# 02_-_Power_Supplies_-_Copy.net
KiCad netlist of a schematic drawn in Altium Designer
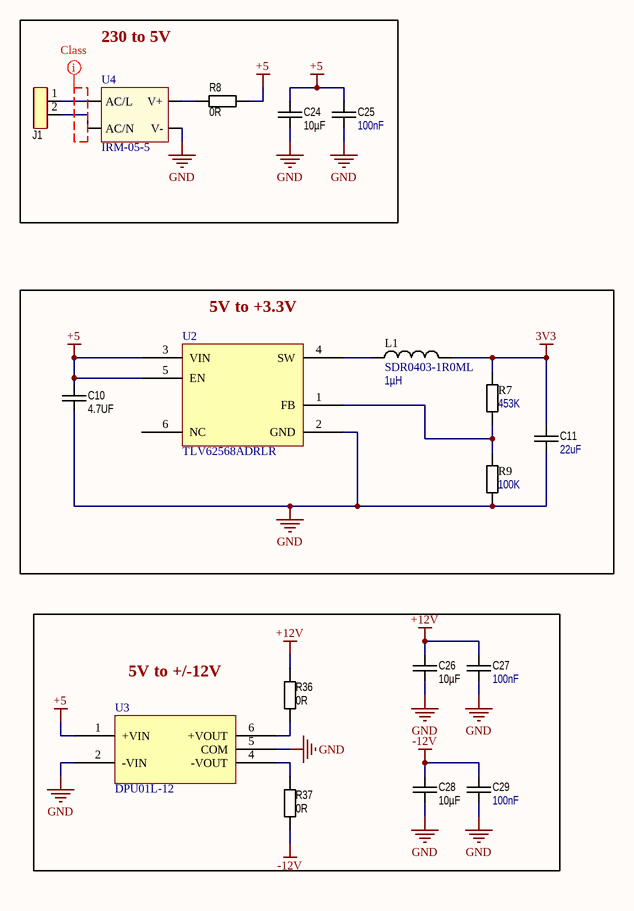
[diagram p0: [02] - Power_Supplies - Copy.SchDoc]

(export (version "E")
  (design (tool "Eeschema 10.0.6"))
  (components
    (comp (ref "C10")
      (value "4.7UF")
      (footprint "CAP 0603/1608")
      (description "4.7µF ±10% 6.3V Ceramic Capacitor X5R 0603 (1608 Metric)")
      (fields (field (name "PARTNUMBER") "C0603C475K9PACTU") (field (name "MANUFACTURER") "KEMET"))
      (libsource (lib "myLibrary") (part "CAPC_4.7UF_0603_6.3V"))
    )
    (comp (ref "C11")
      (value "22uF")
      (footprint "CAP 0603/1608")
      (description "22µF ±20% 6.3V Ceramic Capacitor X5R 0603 (1608 Metric)")
      (fields
        (field (name "PARTNUMBER") "GRM188R60J226MEA0D")
        (field (name "MANUFACTURER") "Murata Electronics")
      )
      (libsource (lib "myLibrary") (part "CAPC_22uF_0603_6.3V"))
    )
    (comp (ref "C24")
      (value "10µF")
      (footprint "CAP 0603/1608")
      (description "10µF ±20% 25V Ceramic Capacitor X5R 0603 (1608 Metric)")
      (fields
        (field (name "PARTNUMBER") "GRM188R61E106MA73D")
        (field (name "MANUFACTURER") "Murata Electronics")
      )
      (libsource (lib "myLibrary") (part "CAPC_10uF_0603_25V"))
    )
    (comp (ref "C25")
      (value "100nF")
      (footprint "CAP 0603/1608")
      (description "0.1µF ±20% 50V Ceramic Capacitor X7R 0603 (1608 Metric)")
      (fields (field (name "PARTNUMBER") "C0603C104M5RACTU") (field (name "MANUFACTURER") "KEMET"))
      (libsource (lib "myLibrary") (part "CAPC_100NF_0603_50V"))
    )
    (comp (ref "C26")
      (value "10µF")
      (footprint "CAP 0603/1608")
      (description "10µF ±20% 25V Ceramic Capacitor X5R 0603 (1608 Metric)")
      (fields
        (field (name "PARTNUMBER") "GRM188R61E106MA73D")
        (field (name "MANUFACTURER") "Murata Electronics")
      )
      (libsource (lib "myLibrary") (part "CAPC_10uF_0603_25V"))
    )
    (comp (ref "C27")
      (value "100nF")
      (footprint "CAP 0603/1608")
      (description "0.1µF ±20% 50V Ceramic Capacitor X7R 0603 (1608 Metric)")
      (fields (field (name "PARTNUMBER") "C0603C104M5RACTU") (field (name "MANUFACTURER") "KEMET"))
      (libsource (lib "myLibrary") (part "CAPC_100NF_0603_50V"))
    )
    (comp (ref "C28")
      (value "10µF")
      (footprint "CAP 0603/1608")
      (description "10µF ±20% 25V Ceramic Capacitor X5R 0603 (1608 Metric)")
      (fields
        (field (name "PARTNUMBER") "GRM188R61E106MA73D")
        (field (name "MANUFACTURER") "Murata Electronics")
      )
      (libsource (lib "myLibrary") (part "CAPC_10uF_0603_25V"))
    )
    (comp (ref "C29")
      (value "100nF")
      (footprint "CAP 0603/1608")
      (description "0.1µF ±20% 50V Ceramic Capacitor X7R 0603 (1608 Metric)")
      (fields (field (name "PARTNUMBER") "C0603C104M5RACTU") (field (name "MANUFACTURER") "KEMET"))
      (libsource (lib "myLibrary") (part "CAPC_100NF_0603_50V"))
    )
    (comp (ref "J1")
      (value "1985195")
      (footprint "BLK_02P_3.5MM")
      (description "2 Position Wire to Board Terminal Block 45° (135°) Angle with Board 0.138\" (3.50mm) Through Hole")
      (fields (field (name "MANUFACTURER") "Phoenix Contact"))
      (libsource (lib "myLibrary") (part "BLK_02_3.5"))
    )
    (comp (ref "L1")
      (value "SDR0403-1R0ML")
      (footprint "IND_NonStandard")
      (description "1µH Unshielded Wirewound Inductor 3.8A 33mOhm Max Nonstandard")
      (fields (field (name "MANUFACTURER") "Bourns Inc.") (field (name "ALTIUM_VALUE") "1µH"))
      (libsource (lib "myLibrary") (part "IND_1uH"))
    )
    (comp (ref "R7")
      (value "453K")
      (footprint "R0603")
      (description "453 kOhms ±0.1% 0.063W, 1/16W Chip Resistor 0603 (1608 Metric) Thin Film")
      (fields
        (field (name "PARTNUMBER") "RN73C1J453KBTD")
        (field (name "MANUFACTURER") "TE Connectivity Passive Product")
      )
      (libsource (lib "myLibrary") (part "RES_453k_0603_0.1%"))
    )
    (comp (ref "R8")
      (value "0R")
      (footprint "R0603")
      (description "RES 0R 0603 JUMPER")
      (fields (field (name "PARTNUMBER") "RC0603JR-070RL") (field (name "MANUFACTURER") "Yageo"))
      (libsource (lib "") (part "RES_0R_0603_JUMPER_1"))
    )
    (comp (ref "R9")
      (value "100K")
      (footprint "R0603")
      (description "100 kOhms ±0.1% 0.1W, 1/10W Chip Resistor 0603 (1608 Metric) Thin Film")
      (fields (field (name "PARTNUMBER") "RT0603BRD07100KL") (field (name "MANUFACTURER") "Yageo"))
      (libsource (lib "myLibrary") (part "RES_100k_0603_0.1%"))
    )
    (comp (ref "R36")
      (value "0R")
      (footprint "R0603")
      (description "RES 0R 0603 JUMPER")
      (fields (field (name "PARTNUMBER") "RC0603JR-070RL") (field (name "MANUFACTURER") "Yageo"))
      (libsource (lib "myLibrary") (part "RES_0R_0603_JUMPER"))
    )
    (comp (ref "R37")
      (value "0R")
      (footprint "R0603")
      (description "RES 0R 0603 JUMPER")
      (fields (field (name "PARTNUMBER") "RC0603JR-070RL") (field (name "MANUFACTURER") "Yageo"))
      (libsource (lib "myLibrary") (part "RES_0R_0603_JUMPER"))
    )
    (comp (ref "U2")
      (value "TLV62568ADRLR")
      (footprint "SOT-563")
      (description "Buck Switching Regulator IC Positive Adjustable 0.6V 1 Output 1A SOT-563, SOT-666")
      (fields (field (name "MANUFACTURER") "Texas Instruments"))
      (libsource (lib "myLibrary") (part "TLV62568ADRLR"))
    )
    (comp (ref "U3")
      (value "DPU01L-12")
      (footprint "SIP7")
      (description "Isolated Module DC DC Converter 2 Output 12V -12V 42mA, 42mA 4.5V - 5.5V Input")
      (fields (field (name "MANUFACTURER") "MEAN WELL USA Inc."))
      (libsource (lib "myLibrary") (part "DC/DC-DPU01L-12"))
    )
    (comp (ref "U4")
      (value "IRM-05-5")
      (footprint "IRM-05-5_DIP-4")
      (description "Enclosed AC DC Converter 1 Output 5V    1A 85 ~ 305 VAC, 120 ~ 430 VDC Input")
      (fields (field (name "MANUFACTURER") "MEAN WELL USA Inc."))
      (libsource (lib "myLibrary") (part "AC/DC-IRM-05-5"))
    )
  )
  (nets
    (net (code "1") (name "+5") (class "Default")
      (node (ref "C10") (pin "1") (pintype "passive"))
      (node (ref "C24") (pin "1") (pintype "passive"))
      (node (ref "C25") (pin "1") (pintype "passive"))
      (node (ref "R8") (pin "2") (pinfunction "2_2") (pintype "passive"))
      (node (ref "U2") (pin "3") (pinfunction "VIN_3") (pintype "passive"))
      (node (ref "U2") (pin "5") (pinfunction "EN_5") (pintype "passive"))
      (node (ref "U3") (pin "1") (pinfunction "+VIN_1") (pintype "passive"))
    )
    (net (code "2") (name "+12V") (class "Default")
      (node (ref "C26") (pin "1") (pintype "passive"))
      (node (ref "C27") (pin "1") (pintype "passive"))
      (node (ref "R36") (pin "2") (pinfunction "2_2") (pintype "passive"))
    )
    (net (code "3") (name "-12V") (class "Default")
      (node (ref "C28") (pin "1") (pintype "passive"))
      (node (ref "C29") (pin "1") (pintype "passive"))
      (node (ref "R37") (pin "1") (pinfunction "1_1") (pintype "passive"))
    )
    (net (code "4") (name "3V3") (class "Default")
      (node (ref "C11") (pin "1") (pintype "passive"))
      (node (ref "L1") (pin "2") (pinfunction "2_2") (pintype "passive"))
      (node (ref "R7") (pin "1") (pinfunction "1_1") (pintype "passive"))
    )
    (net (code "5") (name "GND") (class "Default")
      (node (ref "C10") (pin "2") (pintype "passive"))
      (node (ref "C11") (pin "2") (pintype "passive"))
      (node (ref "C24") (pin "2") (pintype "passive"))
      (node (ref "C25") (pin "2") (pintype "passive"))
      (node (ref "C26") (pin "2") (pintype "passive"))
      (node (ref "C27") (pin "2") (pintype "passive"))
      (node (ref "C28") (pin "2") (pintype "passive"))
      (node (ref "C29") (pin "2") (pintype "passive"))
      (node (ref "R9") (pin "2") (pinfunction "2_2") (pintype "passive"))
      (node (ref "U2") (pin "2") (pinfunction "GND_2") (pintype "passive"))
      (node (ref "U3") (pin "2") (pinfunction "-VIN_2") (pintype "passive"))
      (node (ref "U3") (pin "5") (pinfunction "COM_5") (pintype "passive"))
      (node (ref "U4") (pin "V-") (pinfunction "V-_V-") (pintype "passive"))
    )
    (net (code "6") (name "Net-(J1-Pad1)") (class "Default")
      (node (ref "J1") (pin "1") (pintype "passive"))
      (node (ref "U4") (pin "AC/L") (pinfunction "AC/L_AC/L") (pintype "passive"))
    )
    (net (code "7") (name "Net-(J1-Pad2)") (class "Default")
      (node (ref "J1") (pin "2") (pintype "passive"))
      (node (ref "U4") (pin "AC/N") (pinfunction "AC/N_AC/N") (pintype "passive"))
    )
    (net (code "8") (name "Net-(R8-Pad1)") (class "Default")
      (node (ref "R8") (pin "1") (pinfunction "1_1") (pintype "passive"))
      (node (ref "U4") (pin "V+") (pinfunction "V+_V+") (pintype "passive"))
    )
    (net (code "9") (name "Net-(U2-FB)") (class "Default")
      (node (ref "R7") (pin "2") (pinfunction "2_2") (pintype "passive"))
      (node (ref "R9") (pin "1") (pinfunction "1_1") (pintype "passive"))
      (node (ref "U2") (pin "1") (pinfunction "FB_1") (pintype "passive"))
    )
    (net (code "10") (name "Net-(U2-SW)") (class "Default")
      (node (ref "L1") (pin "1") (pinfunction "1_1") (pintype "passive"))
      (node (ref "U2") (pin "4") (pinfunction "SW_4") (pintype "passive"))
    )
    (net (code "11") (name "Net-(U3-+VOUT)") (class "Default")
      (node (ref "R36") (pin "1") (pinfunction "1_1") (pintype "passive"))
      (node (ref "U3") (pin "6") (pinfunction "+VOUT_6") (pintype "passive"))
    )
    (net (code "12") (name "Net-(U3--VOUT)") (class "Default")
      (node (ref "R37") (pin "2") (pinfunction "2_2") (pintype "passive"))
      (node (ref "U3") (pin "4") (pinfunction "-VOUT_4") (pintype "passive"))
    )
    (net (code "13") (name "unconnected-(U2-NC-Pad6)") (class "Default")
      (node (ref "U2") (pin "6") (pinfunction "NC_6") (pintype "passive"))
    )
  )
)
